# RTU.net
KiCad netlist of a schematic drawn in EAGLE
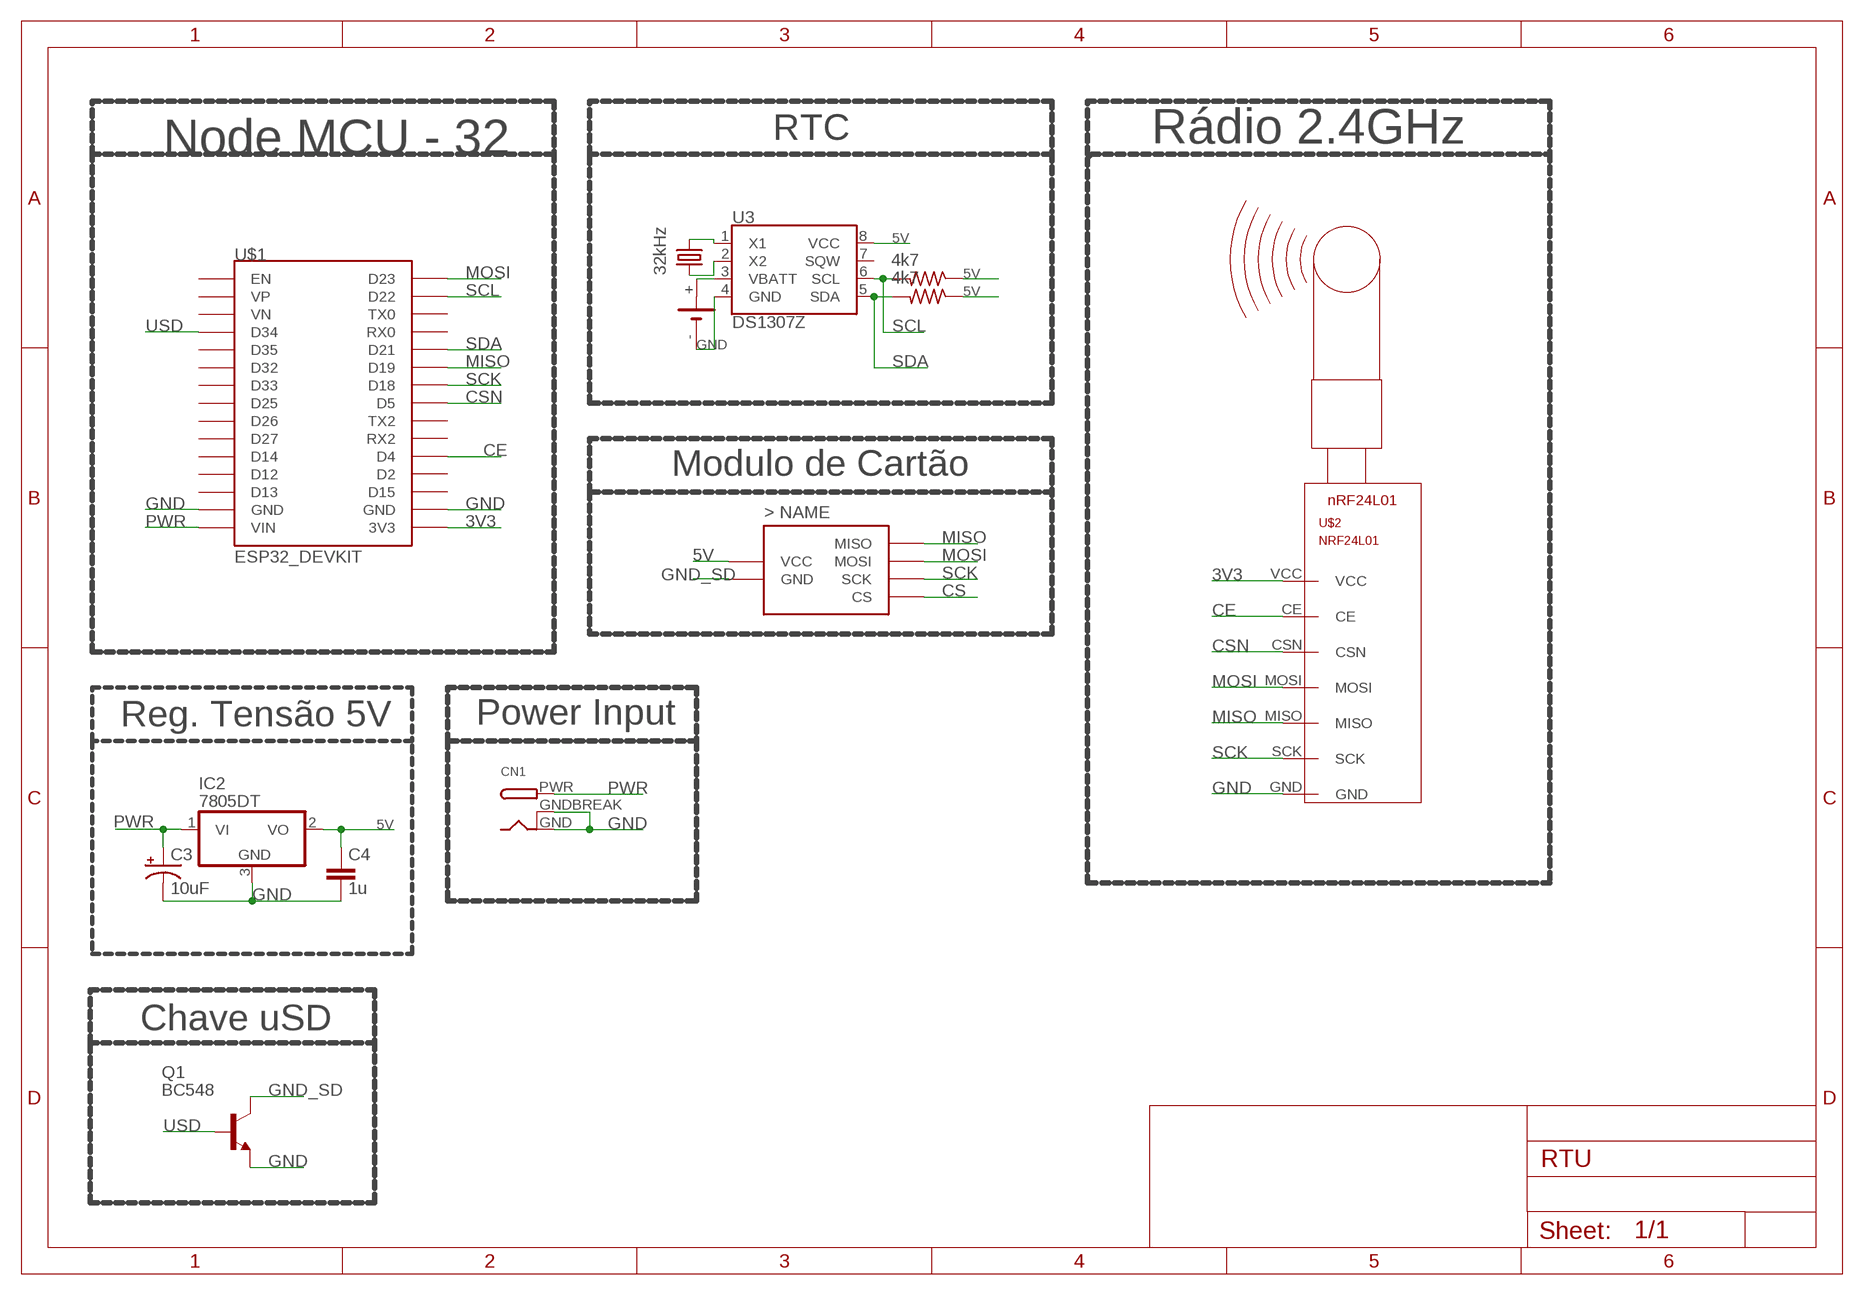
[diagram p0: schematic, sheet 1]

(export (version "E")
  (design (tool "Eeschema 10.0.6"))
  (components
    (comp (ref "C3")
      (value "10uF")
      (footprint "eagle-import:CPOL-RADIAL-2.5MM-5MM")
      (libsource (lib "eagle-import") (part "10UF-POLAR-RADIAL-2.5MM-25V-20%"))
    )
    (comp (ref "C4")
      (value "1u")
      (footprint "eagle-import:C025-024X044")
      (libsource (lib "eagle-import") (part "C-EU025-024X044"))
    )
    (comp (ref "CN1")
      (value "DCBARRELPTH")
      (footprint "eagle-import:DCJACK_2MM_PTH")
      (libsource (lib "eagle-import") (part "DCBARRELPTH"))
    )
    (comp (ref "G2")
      (value "CH291-1220LF")
      (footprint "eagle-import:CH291-1220LF")
      (libsource (lib "eagle-import") (part "CH291-1220LF"))
    )
    (comp (ref "IC2")
      (value "7805DT")
      (footprint "eagle-import:TO252")
      (libsource (lib "eagle-import") (part "78DT05"))
    )
    (comp (ref "Q1")
      (value "BC548")
      (footprint "eagle-import:TO92-EBC")
      (libsource (lib "eagle-import") (part "BC548"))
    )
    (comp (ref "R4")
      (value "4k7")
      (footprint "eagle-import:0204_7")
      (libsource (lib "eagle-import") (part "R-US_0204/7"))
    )
    (comp (ref "R5")
      (value "4k7")
      (footprint "eagle-import:0204_7")
      (libsource (lib "eagle-import") (part "R-US_0204/7"))
    )
    (comp (ref "U$1")
      (value "ESP32_DEVKIT")
      (footprint "eagle-import:ESP32_DEVKIT")
      (libsource (lib "eagle-import") (part "ESP32_DEVKIT"))
    )
    (comp (ref "U$2")
      (value "NRF24L01")
      (footprint "eagle-import:NRF24L01")
      (libsource (lib "eagle-import") (part "NRF24L01"))
    )
    (comp (ref "U2")
      (value "MICROSD_CATALEX")
      (footprint "eagle-import:MICROSD_CATALEX")
      (libsource (lib "eagle-import") (part "MICROSD_CATALEX"))
    )
    (comp (ref "U3")
      (value "DS1307Z")
      (footprint "eagle-import:SO08-0.15")
      (libsource (lib "eagle-import") (part "DS1307Z"))
    )
    (comp (ref "Y2")
      (value "32kHz")
      (footprint "eagle-import:TC38H")
      (libsource (lib "eagle-import") (part "CRYSTALTC38H"))
    )
  )
  (nets
    (net (code "1") (name "/3V3") (class "Default")
      (node (ref "U$1") (pin "3V3") (pinfunction "3V3_3V3") (pintype "bidirectional"))
      (node (ref "U$2") (pin "VCC") (pinfunction "VCC_VCC") (pintype "bidirectional"))
    )
    (net (code "2") (name "/5V") (class "Default")
      (node (ref "C4") (pin "1") (pinfunction "1_1") (pintype "passive"))
      (node (ref "IC2") (pin "2") (pinfunction "VO_2") (pintype "passive"))
      (node (ref "R4") (pin "1") (pinfunction "1_1") (pintype "passive"))
      (node (ref "R5") (pin "1") (pinfunction "1_1") (pintype "passive"))
      (node (ref "U2") (pin "VCC") (pinfunction "VCC_VCC") (pintype "bidirectional"))
      (node (ref "U3") (pin "8") (pinfunction "VCC_8") (pintype "bidirectional"))
    )
    (net (code "3") (name "/CE") (class "Default")
      (node (ref "U$1") (pin "D4") (pinfunction "D4_D4") (pintype "bidirectional"))
      (node (ref "U$2") (pin "CE") (pinfunction "CE_CE") (pintype "bidirectional"))
    )
    (net (code "4") (name "/CS") (class "Default")
      (node (ref "U2") (pin "CS") (pinfunction "CS_CS") (pintype "bidirectional"))
    )
    (net (code "5") (name "/CSN") (class "Default")
      (node (ref "U$1") (pin "D5") (pinfunction "D5_D5") (pintype "bidirectional"))
      (node (ref "U$2") (pin "CSN") (pinfunction "CSN_CSN") (pintype "bidirectional"))
    )
    (net (code "6") (name "/GND") (class "Default")
      (node (ref "C3") (pin "2") (pinfunction "-_2") (pintype "passive"))
      (node (ref "C4") (pin "2") (pinfunction "2_2") (pintype "passive"))
      (node (ref "CN1") (pin "GND") (pinfunction "GND_GND") (pintype "power_in"))
      (node (ref "CN1") (pin "GNDBREAK") (pinfunction "GNDBREAK_GNDBREAK") (pintype "power_in"))
      (node (ref "G2") (pin "-") (pinfunction "-_-") (pintype "passive"))
      (node (ref "IC2") (pin "3") (pinfunction "GND_3") (pintype "passive"))
      (node (ref "Q1") (pin "E") (pinfunction "E_E") (pintype "passive"))
      (node (ref "U$1") (pin "GND@1") (pinfunction "GND_GND@1") (pintype "bidirectional"))
      (node (ref "U$1") (pin "GND@2") (pinfunction "GND_GND@2") (pintype "bidirectional"))
      (node (ref "U$2") (pin "GND") (pinfunction "GND_GND") (pintype "bidirectional"))
      (node (ref "U3") (pin "4") (pinfunction "GND_4") (pintype "bidirectional"))
    )
    (net (code "7") (name "/GND_SD") (class "Default")
      (node (ref "Q1") (pin "C") (pinfunction "C_C") (pintype "passive"))
      (node (ref "U2") (pin "GND") (pinfunction "GND_GND") (pintype "bidirectional"))
    )
    (net (code "8") (name "/MISO") (class "Default")
      (node (ref "U$1") (pin "D19") (pinfunction "D19_D19") (pintype "bidirectional"))
      (node (ref "U$2") (pin "MISO") (pinfunction "MISO_MISO") (pintype "bidirectional"))
      (node (ref "U2") (pin "MISO") (pinfunction "MISO_MISO") (pintype "bidirectional"))
    )
    (net (code "9") (name "/MOSI") (class "Default")
      (node (ref "U$1") (pin "D23") (pinfunction "D23_D23") (pintype "bidirectional"))
      (node (ref "U$2") (pin "MOSI") (pinfunction "MOSI_MOSI") (pintype "bidirectional"))
      (node (ref "U2") (pin "MOSI") (pinfunction "MOSI_MOSI") (pintype "bidirectional"))
    )
    (net (code "10") (name "/PWR") (class "Default")
      (node (ref "C3") (pin "1") (pinfunction "+_1") (pintype "passive"))
      (node (ref "CN1") (pin "PWR") (pinfunction "PWR_PWR") (pintype "power_in"))
      (node (ref "IC2") (pin "1") (pinfunction "VI_1") (pintype "input"))
      (node (ref "U$1") (pin "VIN") (pinfunction "VIN_VIN") (pintype "bidirectional"))
    )
    (net (code "11") (name "/SCK") (class "Default")
      (node (ref "U$1") (pin "D18") (pinfunction "D18_D18") (pintype "bidirectional"))
      (node (ref "U$2") (pin "SCK") (pinfunction "SCK_SCK") (pintype "bidirectional"))
      (node (ref "U2") (pin "SCK") (pinfunction "SCK_SCK") (pintype "bidirectional"))
    )
    (net (code "12") (name "/SCL") (class "Default")
      (node (ref "R4") (pin "2") (pinfunction "2_2") (pintype "passive"))
      (node (ref "U$1") (pin "D22") (pinfunction "D22_D22") (pintype "bidirectional"))
      (node (ref "U3") (pin "6") (pinfunction "SCL_6") (pintype "bidirectional"))
    )
    (net (code "13") (name "/SDA") (class "Default")
      (node (ref "R5") (pin "2") (pinfunction "2_2") (pintype "passive"))
      (node (ref "U$1") (pin "D21") (pinfunction "D21_D21") (pintype "bidirectional"))
      (node (ref "U3") (pin "5") (pinfunction "SDA_5") (pintype "bidirectional"))
    )
    (net (code "14") (name "/USD") (class "Default")
      (node (ref "Q1") (pin "B") (pinfunction "B_B") (pintype "passive"))
      (node (ref "U$1") (pin "D34") (pinfunction "D34_D34") (pintype "bidirectional"))
    )
    (net (code "15") (name "Net-(U3-VBATT)") (class "Default")
      (node (ref "G2") (pin "+") (pinfunction "+_+") (pintype "passive"))
      (node (ref "U3") (pin "3") (pinfunction "VBATT_3") (pintype "bidirectional"))
    )
    (net (code "16") (name "Net-(U3-X1)") (class "Default")
      (node (ref "U3") (pin "1") (pinfunction "X1_1") (pintype "bidirectional"))
      (node (ref "Y2") (pin "2") (pinfunction "2_2") (pintype "passive"))
    )
    (net (code "17") (name "Net-(U3-X2)") (class "Default")
      (node (ref "U3") (pin "2") (pinfunction "X2_2") (pintype "bidirectional"))
      (node (ref "Y2") (pin "1") (pinfunction "1_1") (pintype "passive"))
    )
    (net (code "18") (name "unconnected-(U$1-PadD2)") (class "Default")
      (node (ref "U$1") (pin "D2") (pinfunction "D2_D2") (pintype "bidirectional"))
    )
    (net (code "19") (name "unconnected-(U$1-PadD12)") (class "Default")
      (node (ref "U$1") (pin "D12") (pinfunction "D12_D12") (pintype "bidirectional"))
    )
    (net (code "20") (name "unconnected-(U$1-PadD13)") (class "Default")
      (node (ref "U$1") (pin "D13") (pinfunction "D13_D13") (pintype "bidirectional"))
    )
    (net (code "21") (name "unconnected-(U$1-PadD14)") (class "Default")
      (node (ref "U$1") (pin "D14") (pinfunction "D14_D14") (pintype "bidirectional"))
    )
    (net (code "22") (name "unconnected-(U$1-PadD15)") (class "Default")
      (node (ref "U$1") (pin "D15") (pinfunction "D15_D15") (pintype "bidirectional"))
    )
    (net (code "23") (name "unconnected-(U$1-PadD25)") (class "Default")
      (node (ref "U$1") (pin "D25") (pinfunction "D25_D25") (pintype "bidirectional"))
    )
    (net (code "24") (name "unconnected-(U$1-PadD26)") (class "Default")
      (node (ref "U$1") (pin "D26") (pinfunction "D26_D26") (pintype "bidirectional"))
    )
    (net (code "25") (name "unconnected-(U$1-PadD27)") (class "Default")
      (node (ref "U$1") (pin "D27") (pinfunction "D27_D27") (pintype "bidirectional"))
    )
    (net (code "26") (name "unconnected-(U$1-PadD32)") (class "Default")
      (node (ref "U$1") (pin "D32") (pinfunction "D32_D32") (pintype "bidirectional"))
    )
    (net (code "27") (name "unconnected-(U$1-PadD33)") (class "Default")
      (node (ref "U$1") (pin "D33") (pinfunction "D33_D33") (pintype "bidirectional"))
    )
    (net (code "28") (name "unconnected-(U$1-PadD35)") (class "Default")
      (node (ref "U$1") (pin "D35") (pinfunction "D35_D35") (pintype "bidirectional"))
    )
    (net (code "29") (name "unconnected-(U$1-PadEN)") (class "Default")
      (node (ref "U$1") (pin "EN") (pinfunction "EN_EN") (pintype "bidirectional"))
    )
    (net (code "30") (name "unconnected-(U$1-PadRX0)") (class "Default")
      (node (ref "U$1") (pin "RX0") (pinfunction "RX0_RX0") (pintype "bidirectional"))
    )
    (net (code "31") (name "unconnected-(U$1-PadRX2)") (class "Default")
      (node (ref "U$1") (pin "RX2") (pinfunction "RX2_RX2") (pintype "bidirectional"))
    )
    (net (code "32") (name "unconnected-(U$1-PadTX0)") (class "Default")
      (node (ref "U$1") (pin "TX0") (pinfunction "TX0_TX0") (pintype "bidirectional"))
    )
    (net (code "33") (name "unconnected-(U$1-PadTX2)") (class "Default")
      (node (ref "U$1") (pin "TX2") (pinfunction "TX2_TX2") (pintype "bidirectional"))
    )
    (net (code "34") (name "unconnected-(U$1-PadVN)") (class "Default")
      (node (ref "U$1") (pin "VN") (pinfunction "VN_VN") (pintype "bidirectional"))
    )
    (net (code "35") (name "unconnected-(U$1-PadVP)") (class "Default")
      (node (ref "U$1") (pin "VP") (pinfunction "VP_VP") (pintype "bidirectional"))
    )
    (net (code "36") (name "unconnected-(U3-SQW-Pad7)") (class "Default")
      (node (ref "U3") (pin "7") (pinfunction "SQW_7") (pintype "bidirectional"))
    )
  )
)
